# Sheet1.net
KiCad netlist of a schematic drawn in Altium Designer
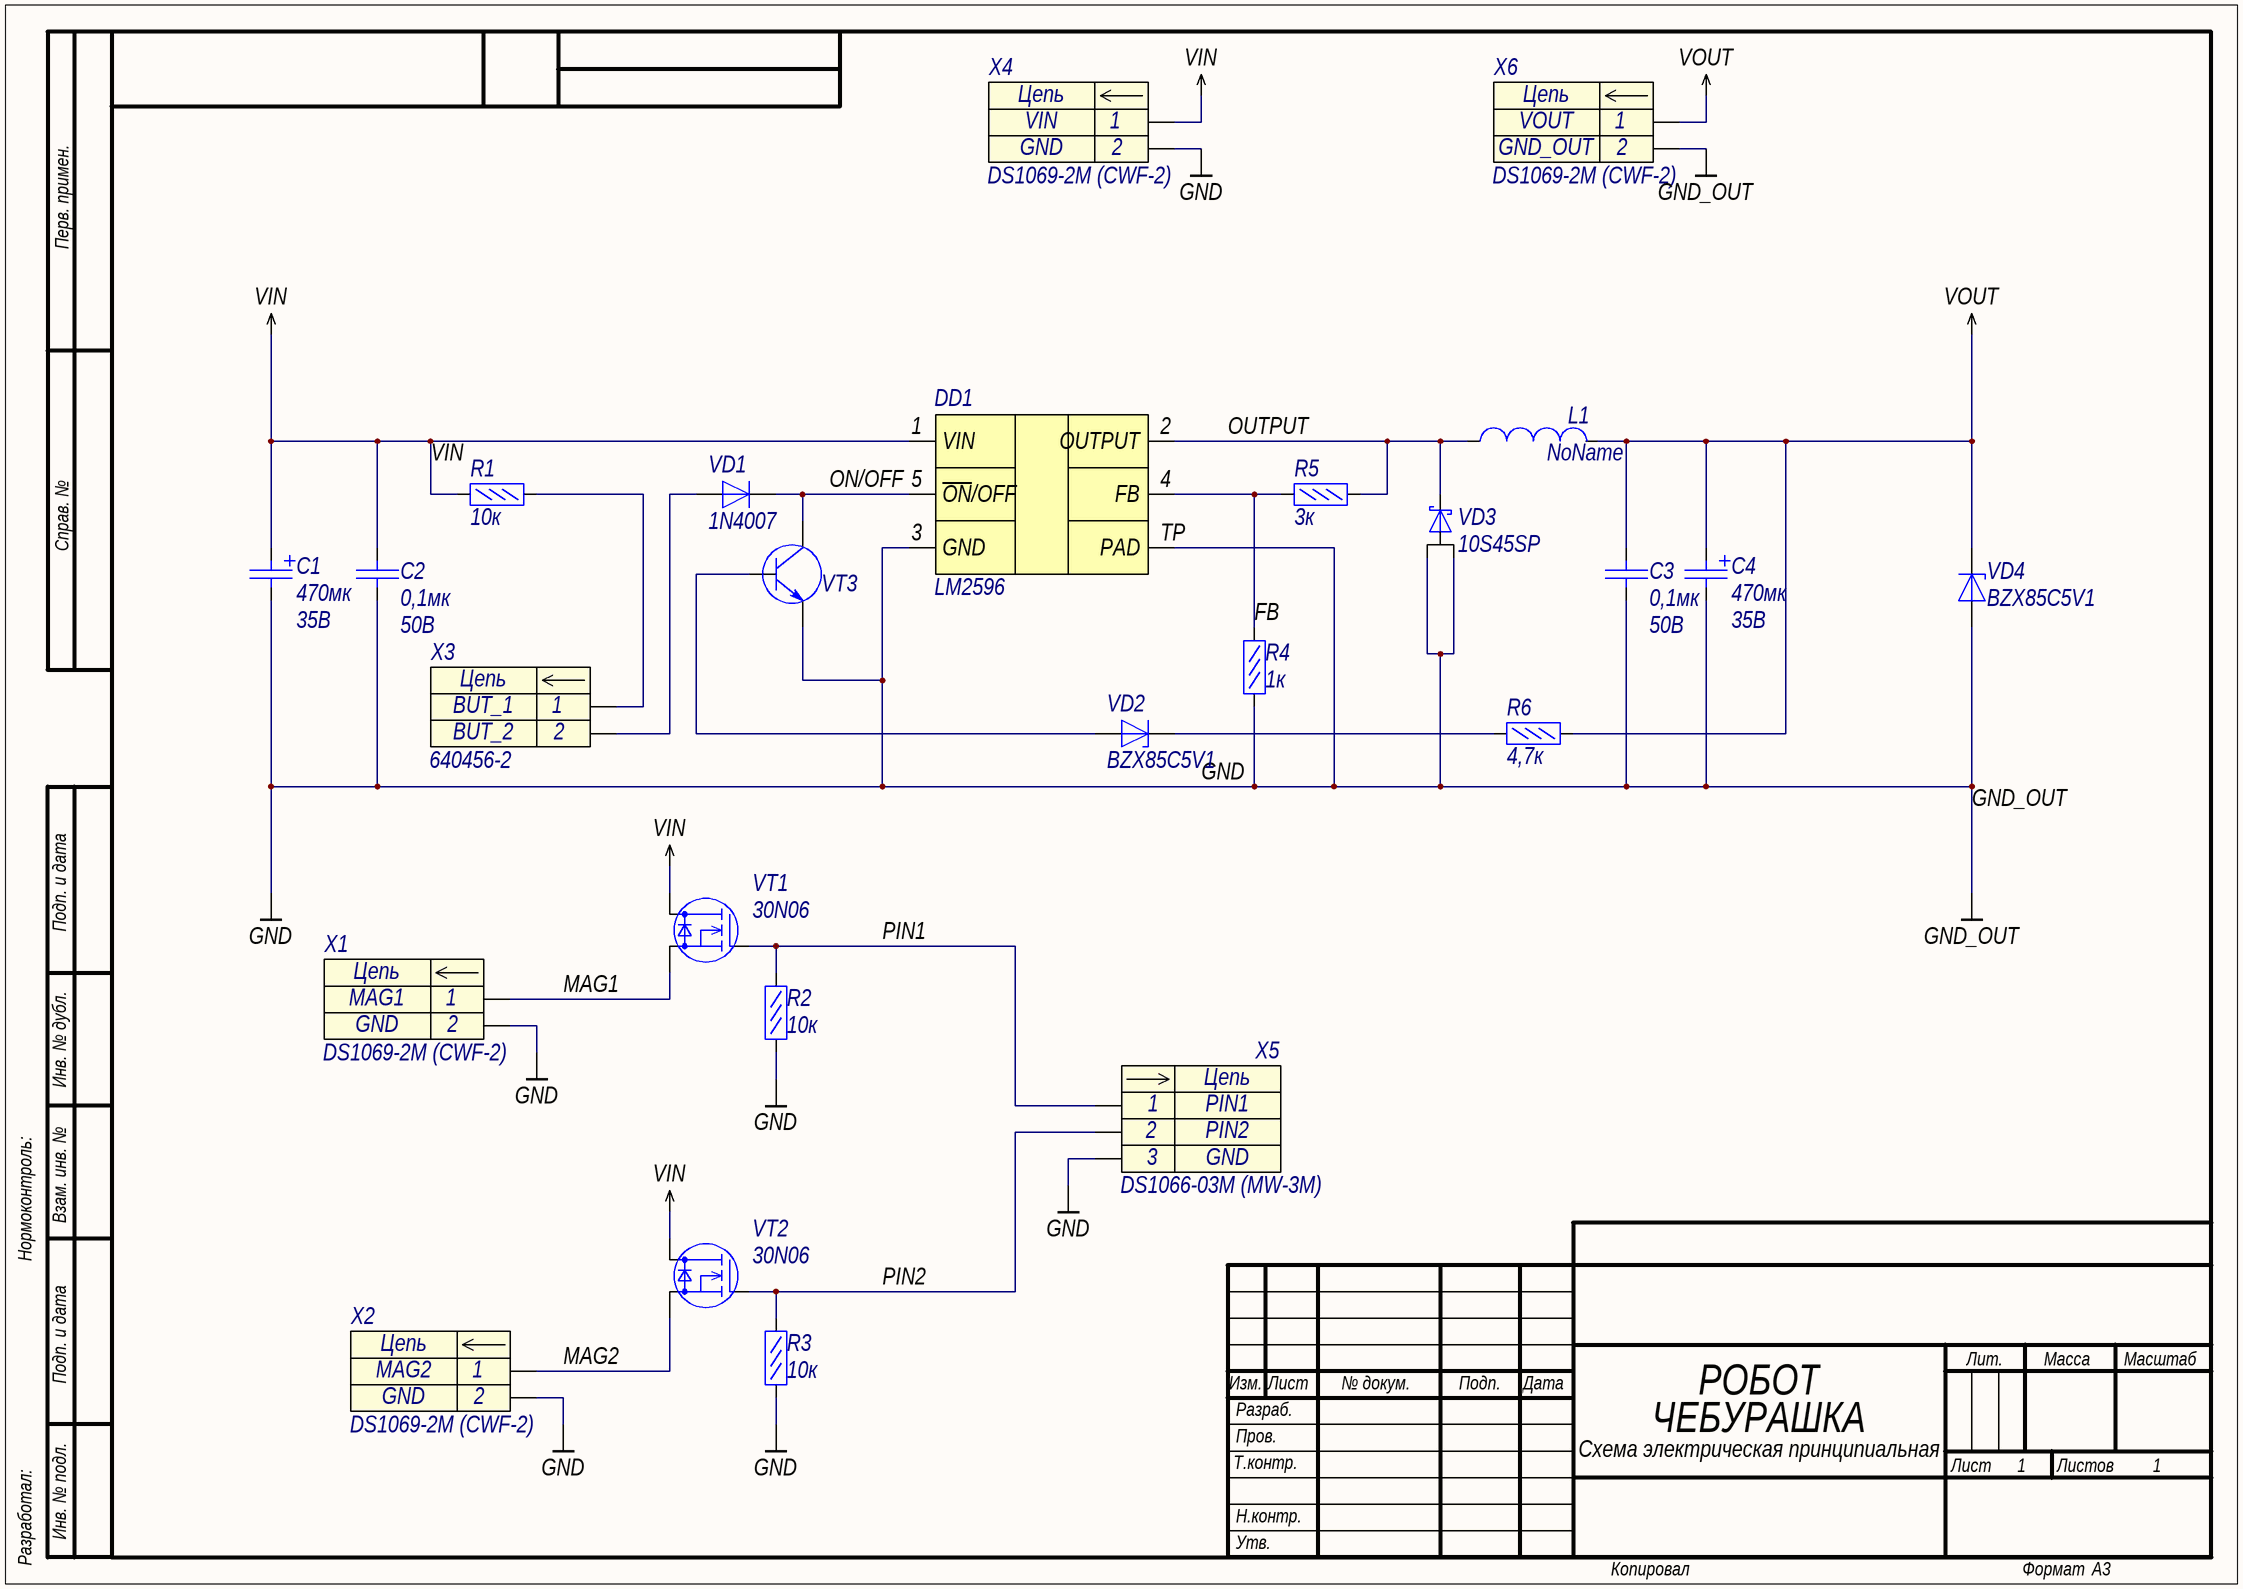
[diagram p0: Sheet1.SchDoc]

(export (version "E")
  (design (tool "Eeschema 10.0.6"))
  (components
    (comp (ref "C1")
      (value "470мк")
      (footprint "CAPALUM_10x12.5")
      (description "Конденсатор эл.лит. алюм. 470мкФ 35В")
      (fields (field (name "MANUFACTURER") "EPCOS") (field (name "VOLTAGE") "35В"))
      (libsource (lib "capacitors") (part "SH035M0470B5s-1015"))
    )
    (comp (ref "C2")
      (value "0,1мк")
      (footprint "C0603")
      (description "Конденсатор кер. 0,1мкФ 50В")
      (fields (field (name "MANUFACTURER") "Yageo") (field (name "VOLTAGE") "50В"))
      (libsource (lib "capacitors") (part "CC0603JPX7R9BB104"))
    )
    (comp (ref "C3")
      (value "0,1мк")
      (footprint "C0603")
      (description "Конденсатор кер. 0,1мкФ 50В")
      (fields (field (name "MANUFACTURER") "Yageo") (field (name "VOLTAGE") "50В"))
      (libsource (lib "capacitors") (part "CC0603JPX7R9BB104"))
    )
    (comp (ref "C4")
      (value "470мк")
      (footprint "CAPALUM_10x12.5")
      (description "Конденсатор эл.лит. алюм. 470мкФ 35В")
      (fields (field (name "MANUFACTURER") "EPCOS") (field (name "VOLTAGE") "35В"))
      (libsource (lib "capacitors") (part "SH035M0470B5s-1015"))
    )
    (comp (ref "DD1")
      (value "LM2596")
      (footprint "D2PAK_5")
      (description "регулируемый стабилизатор напряжения")
      (libsource (lib "ics") (part "LM2596"))
    )
    (comp (ref "L1")
      (value "NoName")
      (footprint "CDRH124")
      (description "Катушка с сердечником 47мкГн 0,8А")
      (libsource (lib "inductance") (part "NoName"))
    )
    (comp (ref "R1")
      (value "10к")
      (footprint "R0603")
      (description "Резистор 10кОм 0,063Вт 1%")
      (fields (field (name "MANUFACTURER") "YAGEO") (field (name "TOLERANCE") "1%"))
      (libsource (lib "resistors") (part "RC0603FR-0710KL"))
    )
    (comp (ref "R2")
      (value "10к")
      (footprint "R0603")
      (description "Резистор 10кОм 0,063Вт 1%")
      (fields (field (name "MANUFACTURER") "YAGEO") (field (name "TOLERANCE") "1%"))
      (libsource (lib "") (part "RC0603FR-0710KL_1"))
    )
    (comp (ref "R3")
      (value "10к")
      (footprint "R0603")
      (description "Резистор 10кОм 0,063Вт 1%")
      (fields (field (name "MANUFACTURER") "YAGEO") (field (name "TOLERANCE") "1%"))
      (libsource (lib "") (part "RC0603FR-0710KL_1"))
    )
    (comp (ref "R4")
      (value "1к")
      (footprint "R0603")
      (description "Резистор 1кОм 0,063Вт 1%")
      (fields (field (name "MANUFACTURER") "YAGEO") (field (name "TOLERANCE") "1%"))
      (libsource (lib "resistors") (part "RC0603FR-071KL"))
    )
    (comp (ref "R5")
      (value "3к")
      (footprint "R0603")
      (description "Резистор 3кОм 0,063Вт 1%")
      (fields (field (name "MANUFACTURER") "YAGEO") (field (name "TOLERANCE") "1%"))
      (libsource (lib "resistors") (part "RC0603FR-073KL"))
    )
    (comp (ref "R6")
      (value "4,7к")
      (footprint "R0603")
      (description "Резистор 4,7кОм 0,063Вт 1%")
      (fields (field (name "MANUFACTURER") "YAGEO") (field (name "TOLERANCE") "1%"))
      (libsource (lib "resistors") (part "RC0603FR-074K7L"))
    )
    (comp (ref "VD1")
      (value "1N4007")
      (footprint "DO-41 VERTICAL")
      (description "Диод выпрямиельный 1000В 1А")
      (libsource (lib "diodes") (part "1N4007"))
    )
    (comp (ref "VD2")
      (value "BZX85C5V1")
      (footprint "DO-41 VERTICAL")
      (description "Стабилитрон 5,1В")
      (libsource (lib "diodes") (part "BZX85C5V1"))
    )
    (comp (ref "VD3")
      (value "10S45SP")
      (footprint "TO-277A")
      (description "Диод Шоттки 45В 10А")
      (fields (field (name "MANUFACTURER") "YFW") (field (name "NAME") "10S45SP"))
      (libsource (lib "diodes") (part "10S45SP"))
    )
    (comp (ref "VD4")
      (value "BZX85C5V1")
      (footprint "DO-41 VERTICAL")
      (description "Стабилитрон 5,1В")
      (libsource (lib "diodes") (part "BZX85C5V1"))
    )
    (comp (ref "VT1")
      (value "30N06")
      (footprint "D-PAK")
      (description "N-MOSFET 60В 30А")
      (fields (field (name "MANUFACTURER") "UMW Youtai Semiconductor") (field (name "NAME") "30N06"))
      (libsource (lib "transistors") (part "30N06"))
    )
    (comp (ref "VT2")
      (value "30N06")
      (footprint "D-PAK")
      (description "N-MOSFET 60В 30А")
      (fields (field (name "MANUFACTURER") "UMW Youtai Semiconductor") (field (name "NAME") "30N06"))
      (libsource (lib "transistors") (part "30N06"))
    )
    (comp (ref "VT3")
      (value "BC847B")
      (footprint "SOT23-3")
      (description "Биполярный NPN транзистор 45В 100мА")
      (fields (field (name "MANUFACTURER") "NXP Semiconductor"))
      (libsource (lib "transistors") (part "BC847B"))
    )
    (comp (ref "X1")
      (value "DS1069-2M (CWF-2)")
      (footprint "CWF-2")
      (description "Разъем - 2 конт. прямая вилка на плату")
      (fields (field (name "NAME") "DS1069-2M (CWF-2)"))
      (libsource (lib "headers") (part "CWF-2"))
    )
    (comp (ref "X2")
      (value "DS1069-2M (CWF-2)")
      (footprint "CWF-2")
      (description "Разъем - 2 конт. прямая вилка на плату")
      (fields (field (name "NAME") "DS1069-2M (CWF-2)"))
      (libsource (lib "headers") (part "CWF-2"))
    )
    (comp (ref "X3")
      (value "640456-2")
      (footprint "JST-640456-2")
      (description "Разъем - 2 конт. прямая вилка на плату")
      (fields (field (name "NAME") "640456-2"))
      (libsource (lib "headers") (part "JST-640456-2"))
    )
    (comp (ref "X4")
      (value "DS1069-2M (CWF-2)")
      (footprint "CWF-2")
      (description "Разъем - 2 конт. прямая вилка на плату")
      (fields (field (name "NAME") "DS1069-2M (CWF-2)"))
      (libsource (lib "headers") (part "CWF-2"))
    )
    (comp (ref "X5")
      (value "DS1066-03M (MW-3M)")
      (footprint "MW-3M")
      (description "Разъем - 3 конт. прямая вилка на плату")
      (fields (field (name "NAME") "DS1066-03M (MW-3M)"))
      (libsource (lib "headers") (part "MW-3M"))
    )
    (comp (ref "X6")
      (value "DS1069-2M (CWF-2)")
      (footprint "CWF-2")
      (description "Разъем - 2 конт. прямая вилка на плату")
      (fields (field (name "NAME") "DS1069-2M (CWF-2)"))
      (libsource (lib "headers") (part "CWF-2"))
    )
  )
  (nets
    (net (code "1") (name "/FB") (class "Default")
      (node (ref "DD1") (pin "4") (pinfunction "FB_4") (pintype "passive"))
      (node (ref "R4") (pin "2") (pinfunction "2_2") (pintype "passive"))
      (node (ref "R5") (pin "1") (pinfunction "1_1") (pintype "passive"))
    )
    (net (code "2") (name "/MAG1") (class "Default")
      (node (ref "VT1") (pin "2") (pinfunction "S_2") (pintype "passive"))
      (node (ref "X1") (pin "1") (pinfunction "1_1") (pintype "passive"))
    )
    (net (code "3") (name "/MAG2") (class "Default")
      (node (ref "VT2") (pin "2") (pinfunction "S_2") (pintype "passive"))
      (node (ref "X2") (pin "1") (pinfunction "1_1") (pintype "passive"))
    )
    (net (code "4") (name "/ON{slash}OFF") (class "Default")
      (node (ref "DD1") (pin "5") (pinfunction "~{ON}/OFF_5") (pintype "passive"))
      (node (ref "VD1") (pin "2") (pinfunction "K_2") (pintype "passive"))
      (node (ref "VT3") (pin "3") (pintype "passive"))
    )
    (net (code "5") (name "/OUTPUT") (class "Default")
      (node (ref "DD1") (pin "2") (pinfunction "OUTPUT_2") (pintype "passive"))
      (node (ref "L1") (pin "1") (pinfunction "3_1") (pintype "passive"))
      (node (ref "R5") (pin "2") (pinfunction "2_2") (pintype "passive"))
      (node (ref "VD3") (pin "3") (pinfunction "K_3") (pintype "passive"))
    )
    (net (code "6") (name "/PIN1") (class "Default")
      (node (ref "R2") (pin "2") (pinfunction "2_2") (pintype "passive"))
      (node (ref "VT1") (pin "1") (pinfunction "G_1") (pintype "passive"))
      (node (ref "X5") (pin "1") (pinfunction "1_1") (pintype "passive"))
    )
    (net (code "7") (name "/PIN2") (class "Default")
      (node (ref "R3") (pin "2") (pinfunction "2_2") (pintype "passive"))
      (node (ref "VT2") (pin "1") (pinfunction "G_1") (pintype "passive"))
      (node (ref "X5") (pin "2") (pinfunction "2_2") (pintype "passive"))
    )
    (net (code "8") (name "GND") (class "Default")
      (node (ref "C1") (pin "2") (pinfunction "2_2") (pintype "passive"))
      (node (ref "C2") (pin "1") (pinfunction "1_1") (pintype "passive"))
      (node (ref "C3") (pin "1") (pinfunction "1_1") (pintype "passive"))
      (node (ref "C4") (pin "2") (pinfunction "2_2") (pintype "passive"))
      (node (ref "DD1") (pin "3") (pinfunction "GND_3") (pintype "passive"))
      (node (ref "DD1") (pin "TP") (pinfunction "PAD_TP") (pintype "passive"))
      (node (ref "R2") (pin "1") (pinfunction "1_1") (pintype "passive"))
      (node (ref "R3") (pin "1") (pinfunction "1_1") (pintype "passive"))
      (node (ref "R4") (pin "1") (pinfunction "1_1") (pintype "passive"))
      (node (ref "VD3") (pin "1") (pinfunction "A_1") (pintype "passive"))
      (node (ref "VD3") (pin "2") (pinfunction "A_2") (pintype "passive"))
      (node (ref "VD4") (pin "1") (pinfunction "A_1") (pintype "passive"))
      (node (ref "VT3") (pin "2") (pintype "passive"))
      (node (ref "X1") (pin "2") (pinfunction "2_2") (pintype "passive"))
      (node (ref "X2") (pin "2") (pinfunction "2_2") (pintype "passive"))
      (node (ref "X4") (pin "2") (pinfunction "2_2") (pintype "passive"))
      (node (ref "X5") (pin "3") (pinfunction "3_3") (pintype "passive"))
      (node (ref "X6") (pin "2") (pinfunction "2_2") (pintype "passive"))
    )
    (net (code "9") (name "Net-(R1-Pad2)") (class "Default")
      (node (ref "R1") (pin "2") (pinfunction "2_2") (pintype "passive"))
      (node (ref "X3") (pin "1") (pinfunction "1_1") (pintype "passive"))
    )
    (net (code "10") (name "Net-(VD1-A)") (class "Default")
      (node (ref "VD1") (pin "1") (pinfunction "A_1") (pintype "passive"))
      (node (ref "X3") (pin "2") (pinfunction "2_2") (pintype "passive"))
    )
    (net (code "11") (name "Net-(VD2-A)") (class "Default")
      (node (ref "VD2") (pin "1") (pinfunction "A_1") (pintype "passive"))
      (node (ref "VT3") (pin "1") (pintype "passive"))
    )
    (net (code "12") (name "Net-(VD2-K)") (class "Default")
      (node (ref "R6") (pin "1") (pinfunction "1_1") (pintype "passive"))
      (node (ref "VD2") (pin "2") (pinfunction "K_2") (pintype "passive"))
    )
    (net (code "13") (name "VIN") (class "Default")
      (node (ref "C1") (pin "1") (pinfunction "1_1") (pintype "passive"))
      (node (ref "C2") (pin "2") (pinfunction "2_2") (pintype "passive"))
      (node (ref "DD1") (pin "1") (pinfunction "VIN_1") (pintype "passive"))
      (node (ref "R1") (pin "1") (pinfunction "1_1") (pintype "passive"))
      (node (ref "VT1") (pin "3") (pinfunction "D_3") (pintype "passive"))
      (node (ref "VT2") (pin "3") (pinfunction "D_3") (pintype "passive"))
      (node (ref "X4") (pin "1") (pinfunction "1_1") (pintype "passive"))
    )
    (net (code "14") (name "VOUT") (class "Default")
      (node (ref "C3") (pin "2") (pinfunction "2_2") (pintype "passive"))
      (node (ref "C4") (pin "1") (pinfunction "1_1") (pintype "passive"))
      (node (ref "L1") (pin "2") (pinfunction "4_2") (pintype "passive"))
      (node (ref "R6") (pin "2") (pinfunction "2_2") (pintype "passive"))
      (node (ref "VD4") (pin "2") (pinfunction "K_2") (pintype "passive"))
      (node (ref "X6") (pin "1") (pinfunction "1_1") (pintype "passive"))
    )
  )
)
